# M2-RS485.net
KiCad netlist of a schematic drawn in Altium Designer
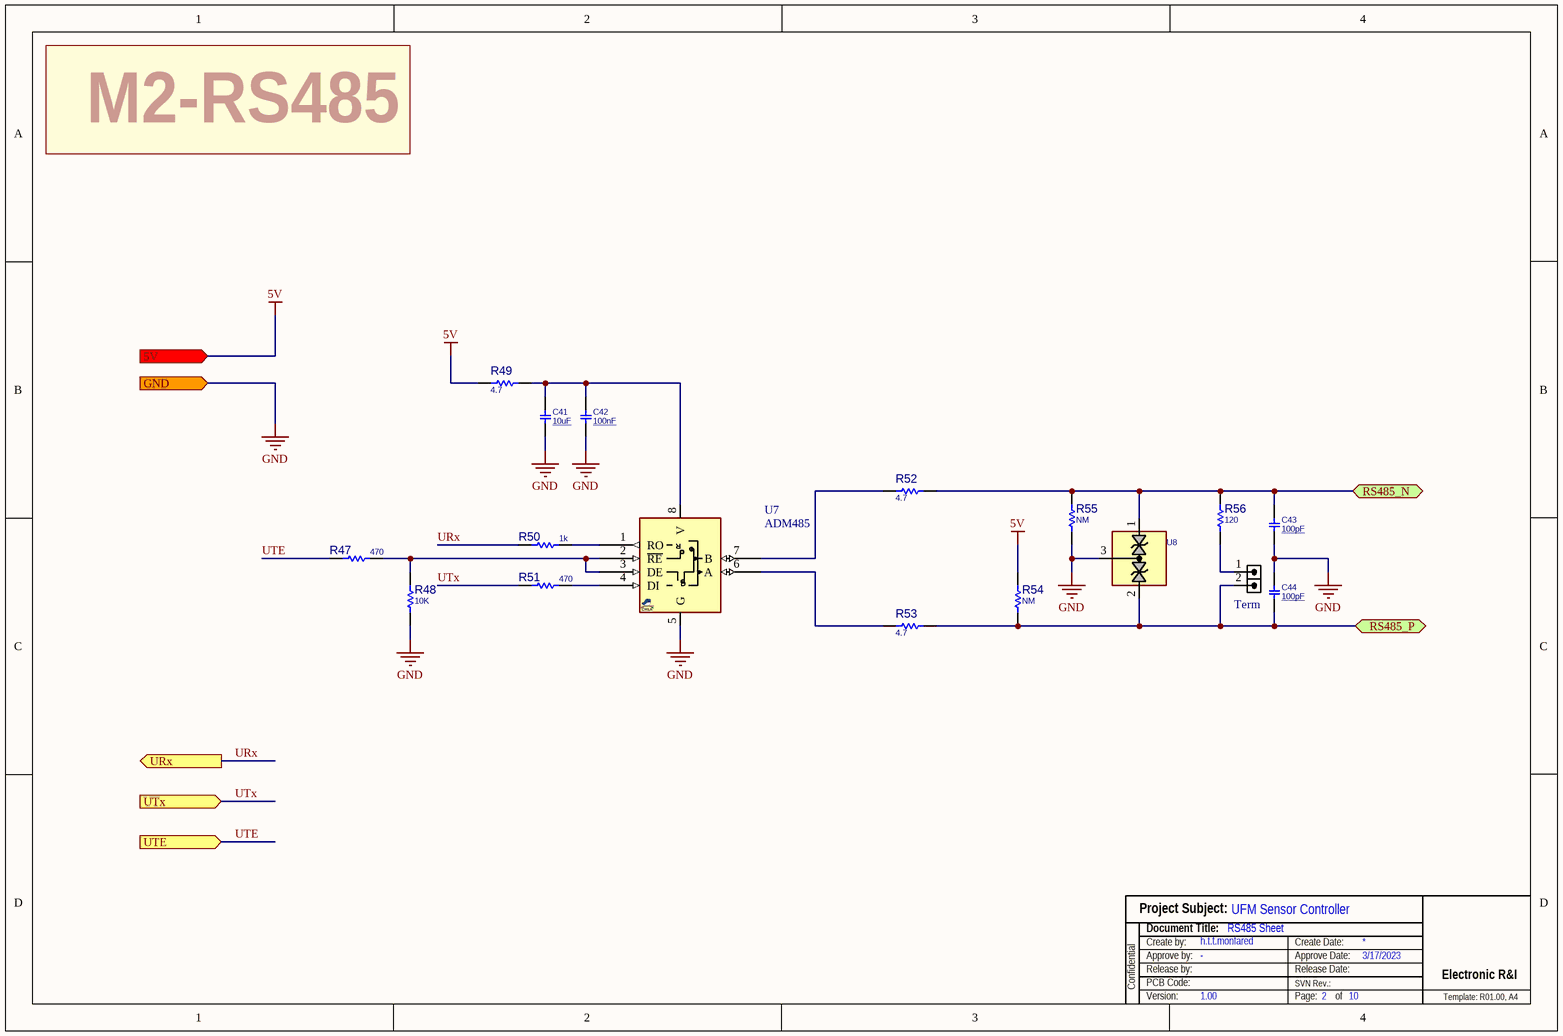
[diagram p0: M2-RS485.SchDoc]

(export (version "E")
  (design (tool "Eeschema 10.0.6"))
  (components
    (comp (ref "C41")
      (value "10uF")
      (footprint "C1206")
      (description "CAP, MLCC, 1nF, 50V, C0G, 10%, 0402")
      (fields (field (name "MANF_P#") "MANF_PART#") (field (name "MANF") "Murata"))
      (libsource (lib "passive_smd") (part "CAP_SMD_MLCC"))
    )
    (comp (ref "C42")
      (value "100nF")
      (footprint "C1206")
      (description "CAP, MLCC, 1nF, 50V, C0G, 10%, 0402")
      (fields (field (name "MANF_P#") "MANF_PART#") (field (name "MANF") "Murata"))
      (libsource (lib "passive_smd") (part "CAP_SMD_MLCC"))
    )
    (comp (ref "C43")
      (value "100pF")
      (footprint "C1206")
      (description "CAP, MLCC, 1nF, 50V, C0G, 10%, 0402")
      (fields (field (name "MANF_P#") "MANF_PART#") (field (name "MANF") "Murata"))
      (libsource (lib "passive_smd") (part "CAP_SMD_MLCC"))
    )
    (comp (ref "C44")
      (value "100pF")
      (footprint "C1206")
      (description "CAP, MLCC, 1nF, 50V, C0G, 10%, 0402")
      (fields (field (name "MANF_P#") "MANF_PART#") (field (name "MANF") "Murata"))
      (libsource (lib "passive_smd") (part "CAP_SMD_MLCC"))
    )
    (comp (ref "R47")
      (value "470")
      (footprint "R1206")
      (description "RESISTOR, SMD")
      (libsource (lib "passive_smd") (part "RES_SMD"))
    )
    (comp (ref "R48")
      (value "10K")
      (footprint "R1206")
      (description "RESISTOR, SMD")
      (libsource (lib "passive_smd") (part "RES_SMD"))
    )
    (comp (ref "R49")
      (value "4.7")
      (footprint "R1206")
      (description "RESISTOR, SMD")
      (libsource (lib "passive_smd") (part "RES_SMD"))
    )
    (comp (ref "R50")
      (value "1k")
      (footprint "R1206")
      (description "RESISTOR, SMD")
      (libsource (lib "passive_smd") (part "RES_SMD"))
    )
    (comp (ref "R51")
      (value "470")
      (footprint "R1206")
      (description "RESISTOR, SMD")
      (libsource (lib "passive_smd") (part "RES_SMD"))
    )
    (comp (ref "R52")
      (value "4.7")
      (footprint "R1206")
      (description "RESISTOR, SMD")
      (libsource (lib "passive_smd") (part "RES_SMD"))
    )
    (comp (ref "R53")
      (value "4.7")
      (footprint "R1206")
      (description "RESISTOR, SMD")
      (libsource (lib "passive_smd") (part "RES_SMD"))
    )
    (comp (ref "R54")
      (value "NM")
      (footprint "R1206")
      (description "RESISTOR, SMD")
      (libsource (lib "passive_smd") (part "RES_SMD"))
    )
    (comp (ref "R55")
      (value "NM")
      (footprint "R1206")
      (description "RESISTOR, SMD")
      (libsource (lib "passive_smd") (part "RES_SMD"))
    )
    (comp (ref "R56")
      (value "120")
      (footprint "R1206")
      (description "RESISTOR, SMD")
      (libsource (lib "passive_smd") (part "RES_SMD"))
    )
    (comp (ref "Term")
      (value "HDRM2")
      (footprint "HDR_M_1X2")
      (description "CONN, HEADER, Male, pitch: 2.54mm, 2POS")
      (libsource (lib "conn_header_2.54mm_st") (part "HDR_M_1X2"))
    )
    (comp (ref "U7")
      (value "ADM485")
      (footprint "SO_8")
      (description "RS-485 Transceiver, 5V, SOP-8, ±7V Ground Difference Between Devices on the Bus")
      (fields (field (name "MANF_P#") "ADM485AR") (field (name "MANF") "Analog Devices"))
      (libsource (lib "rs485-422") (part "ADM485_SOP8"))
    )
    (comp (ref "U8")
      (value "CDSOT23-SM712")
      (footprint "SOT23_3")
      (description "TVS, ESD PROTECT, 2CH, 400W/17A PP, 7.5VBR, ±8KV ESDmin")
      (fields (field (name "MANF") "Bourns"))
      (libsource (lib "protect_tvs_esd_fuse") (part "TVS_X2_CDSOT23-SM712"))
    )
  )
  (nets
    (net (code "1") (name "/RS485_N") (class "Default")
      (node (ref "C43") (pin "2") (pinfunction "2_2") (pintype "passive"))
      (node (ref "R52") (pin "2") (pinfunction "2_2") (pintype "passive"))
      (node (ref "R55") (pin "2") (pinfunction "2_2") (pintype "passive"))
      (node (ref "R56") (pin "2") (pinfunction "2_2") (pintype "passive"))
      (node (ref "U8") (pin "1") (pinfunction "NC_1") (pintype "passive"))
    )
    (net (code "2") (name "/RS485_P") (class "Default")
      (node (ref "C44") (pin "1") (pinfunction "1_1") (pintype "passive"))
      (node (ref "R53") (pin "2") (pinfunction "2_2") (pintype "passive"))
      (node (ref "R54") (pin "1") (pinfunction "1_1") (pintype "passive"))
      (node (ref "Term") (pin "2") (pinfunction "2_2") (pintype "passive"))
      (node (ref "U8") (pin "2") (pinfunction "GND_2") (pintype "passive"))
    )
    (net (code "3") (name "/URx") (class "Default")
      (node (ref "R50") (pin "1") (pinfunction "1_1") (pintype "passive"))
    )
    (net (code "4") (name "/UTE") (class "Default")
      (node (ref "R47") (pin "1") (pinfunction "1_1") (pintype "passive"))
    )
    (net (code "5") (name "/UTx") (class "Default")
      (node (ref "R51") (pin "1") (pinfunction "1_1") (pintype "passive"))
    )
    (net (code "6") (name "5V") (class "Default")
      (node (ref "R49") (pin "2") (pinfunction "2_2") (pintype "passive"))
      (node (ref "R54") (pin "2") (pinfunction "2_2") (pintype "passive"))
    )
    (net (code "7") (name "GND") (class "Default")
      (node (ref "C41") (pin "1") (pinfunction "1_1") (pintype "passive"))
      (node (ref "C42") (pin "1") (pinfunction "1_1") (pintype "passive"))
      (node (ref "C43") (pin "1") (pinfunction "1_1") (pintype "passive"))
      (node (ref "C44") (pin "2") (pinfunction "2_2") (pintype "passive"))
      (node (ref "R48") (pin "1") (pinfunction "1_1") (pintype "passive"))
      (node (ref "R55") (pin "1") (pinfunction "1_1") (pintype "passive"))
      (node (ref "U7") (pin "5") (pinfunction "G_5") (pintype "passive"))
      (node (ref "U8") (pin "3") (pinfunction "NC_3") (pintype "passive"))
    )
    (net (code "8") (name "Net-(R56-Pad1)") (class "Default")
      (node (ref "R56") (pin "1") (pinfunction "1_1") (pintype "passive"))
      (node (ref "Term") (pin "1") (pinfunction "1_1") (pintype "passive"))
    )
    (net (code "9") (name "Net-(U7-A)") (class "Default")
      (node (ref "R53") (pin "1") (pinfunction "1_1") (pintype "passive"))
      (node (ref "U7") (pin "6") (pinfunction "A_6") (pintype "bidirectional"))
    )
    (net (code "10") (name "Net-(U7-B)") (class "Default")
      (node (ref "R52") (pin "1") (pinfunction "1_1") (pintype "passive"))
      (node (ref "U7") (pin "7") (pinfunction "B_7") (pintype "bidirectional"))
    )
    (net (code "11") (name "Net-(U7-DE)") (class "Default")
      (node (ref "R47") (pin "2") (pinfunction "2_2") (pintype "passive"))
      (node (ref "R48") (pin "2") (pinfunction "2_2") (pintype "passive"))
      (node (ref "U7") (pin "2") (pinfunction "~{RE}_2") (pintype "input"))
      (node (ref "U7") (pin "3") (pinfunction "DE_3") (pintype "input"))
    )
    (net (code "12") (name "Net-(U7-DI)") (class "Default")
      (node (ref "R51") (pin "2") (pinfunction "2_2") (pintype "passive"))
      (node (ref "U7") (pin "4") (pinfunction "DI_4") (pintype "input"))
    )
    (net (code "13") (name "Net-(U7-RO)") (class "Default")
      (node (ref "R50") (pin "2") (pinfunction "2_2") (pintype "passive"))
      (node (ref "U7") (pin "1") (pinfunction "RO_1") (pintype "output"))
    )
    (net (code "14") (name "Net-(U7-V)") (class "Default")
      (node (ref "C41") (pin "2") (pinfunction "2_2") (pintype "passive"))
      (node (ref "C42") (pin "2") (pinfunction "2_2") (pintype "passive"))
      (node (ref "R49") (pin "1") (pinfunction "1_1") (pintype "passive"))
      (node (ref "U7") (pin "8") (pinfunction "V_8") (pintype "passive"))
    )
  )
)
